# heatingHeader.net
KiCad netlist of a schematic drawn in EAGLE
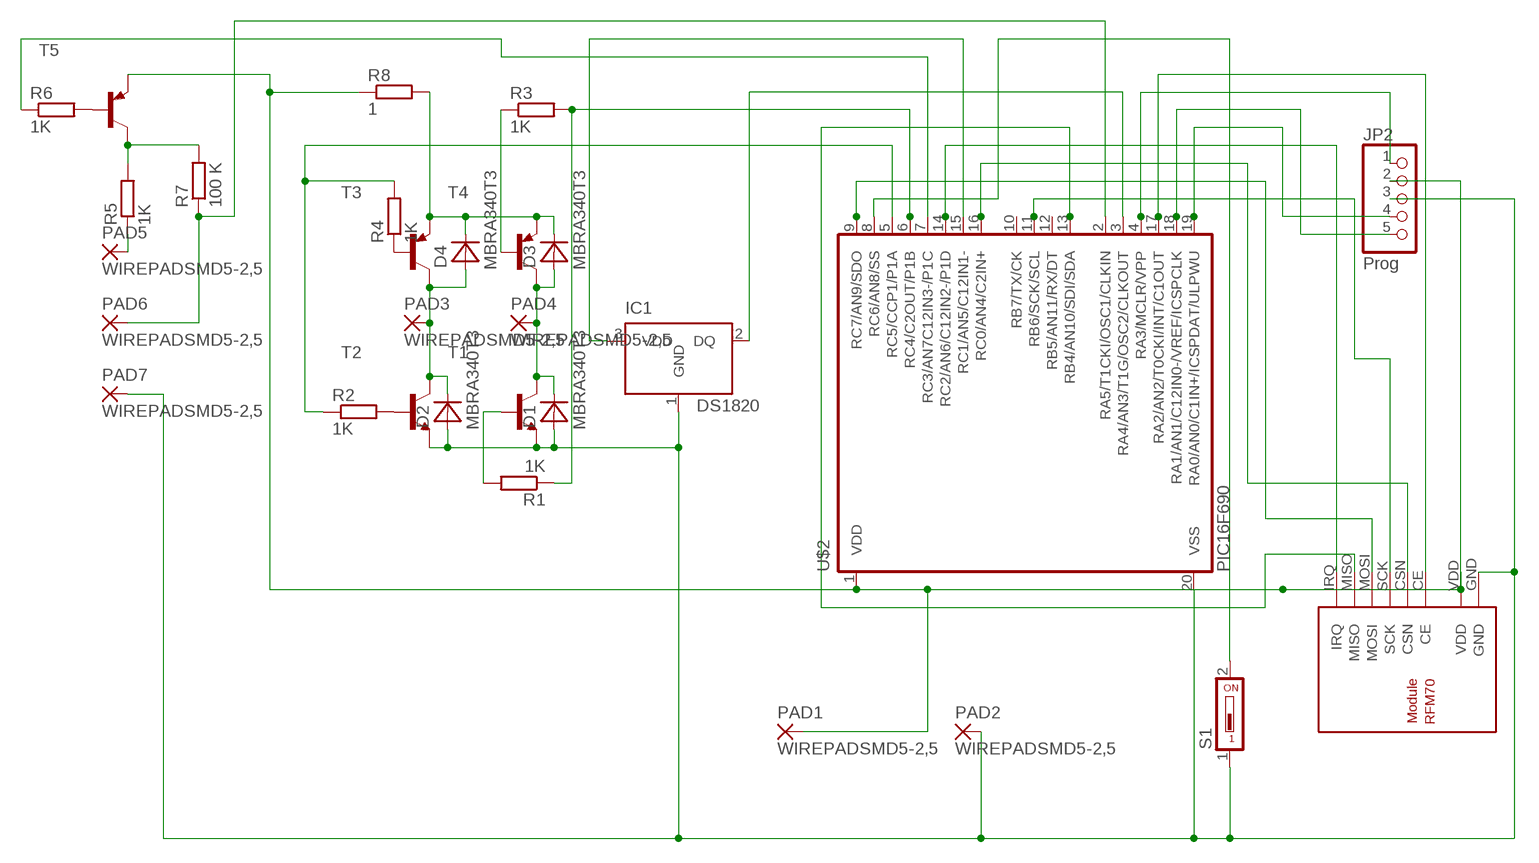
[diagram p0: schematic, sheet 1]

(export (version "E")
  (design (tool "Eeschema 10.0.6"))
  (components
    (comp (ref "D1")
      (value "MBRA340T3")
      (footprint "eagle-import:SMA")
      (libsource (lib "eagle-import") (part "MBRA340T3"))
    )
    (comp (ref "D2")
      (value "MBRA340T3")
      (footprint "eagle-import:SMA")
      (libsource (lib "eagle-import") (part "MBRA340T3"))
    )
    (comp (ref "D3")
      (value "MBRA340T3")
      (footprint "eagle-import:SMA")
      (libsource (lib "eagle-import") (part "MBRA340T3"))
    )
    (comp (ref "D4")
      (value "MBRA340T3")
      (footprint "eagle-import:SMA")
      (libsource (lib "eagle-import") (part "MBRA340T3"))
    )
    (comp (ref "IC1")
      (value "DS1820")
      (footprint "eagle-import:TO-92")
      (libsource (lib "eagle-import") (part "DS1820"))
    )
    (comp (ref "JP2")
      (value "Prog")
      (footprint "eagle-import:1X05")
      (libsource (lib "eagle-import") (part "PINHD-1X5"))
    )
    (comp (ref "PAD1")
      (value "WIREPADSMD5-2,5")
      (footprint "eagle-import:5-2,5")
      (libsource (lib "eagle-import") (part "WIREPADSMD5-2,5"))
    )
    (comp (ref "PAD2")
      (value "WIREPADSMD5-2,5")
      (footprint "eagle-import:5-2,5")
      (libsource (lib "eagle-import") (part "WIREPADSMD5-2,5"))
    )
    (comp (ref "PAD3")
      (value "WIREPADSMD5-2,5")
      (footprint "eagle-import:5-2,5")
      (libsource (lib "eagle-import") (part "WIREPADSMD5-2,5"))
    )
    (comp (ref "PAD4")
      (value "WIREPADSMD5-2,5")
      (footprint "eagle-import:5-2,5")
      (libsource (lib "eagle-import") (part "WIREPADSMD5-2,5"))
    )
    (comp (ref "PAD5")
      (value "WIREPADSMD5-2,5")
      (footprint "eagle-import:5-2,5")
      (libsource (lib "eagle-import") (part "WIREPADSMD5-2,5"))
    )
    (comp (ref "PAD6")
      (value "WIREPADSMD5-2,5")
      (footprint "eagle-import:5-2,5")
      (libsource (lib "eagle-import") (part "WIREPADSMD5-2,5"))
    )
    (comp (ref "PAD7")
      (value "WIREPADSMD5-2,5")
      (footprint "eagle-import:5-2,5")
      (libsource (lib "eagle-import") (part "WIREPADSMD5-2,5"))
    )
    (comp (ref "R1")
      (value "1K")
      (footprint "eagle-import:R1206")
      (libsource (lib "eagle-import") (part "R-EU_R1206"))
    )
    (comp (ref "R2")
      (value "1K")
      (footprint "eagle-import:R1206")
      (libsource (lib "eagle-import") (part "R-EU_R1206"))
    )
    (comp (ref "R3")
      (value "1K")
      (footprint "eagle-import:R1206")
      (libsource (lib "eagle-import") (part "R-EU_R1206"))
    )
    (comp (ref "R4")
      (value "1K")
      (footprint "eagle-import:R1206")
      (libsource (lib "eagle-import") (part "R-EU_R1206"))
    )
    (comp (ref "R5")
      (value "1K")
      (footprint "eagle-import:R1206")
      (libsource (lib "eagle-import") (part "R-EU_R1206"))
    )
    (comp (ref "R6")
      (value "1K")
      (footprint "eagle-import:R1206")
      (libsource (lib "eagle-import") (part "R-EU_R1206"))
    )
    (comp (ref "R7")
      (value "100 K")
      (footprint "eagle-import:R1206")
      (libsource (lib "eagle-import") (part "R-EU_R1206"))
    )
    (comp (ref "R8")
      (value "1")
      (footprint "eagle-import:R0805W")
      (libsource (lib "eagle-import") (part "R-EU_R0805W"))
    )
    (comp (ref "S1")
      (value "SD4-01")
      (footprint "eagle-import:SD4-01")
      (libsource (lib "eagle-import") (part "SD4-01"))
    )
    (comp (ref "T1")
      (value "BC817-40-NPN-SOT23-BEC")
      (footprint "eagle-import:SOT23-BEC")
      (libsource (lib "eagle-import") (part "-NPN-SOT23-BECBC817-40"))
    )
    (comp (ref "T2")
      (value "BC817-40-NPN-SOT23-BEC")
      (footprint "eagle-import:SOT23-BEC")
      (libsource (lib "eagle-import") (part "-NPN-SOT23-BECBC817-40"))
    )
    (comp (ref "T3")
      (value "BC807-16-PNP-SOT23-BEC")
      (footprint "eagle-import:SOT23-BEC")
      (libsource (lib "eagle-import") (part "-PNP-SOT23-BECBC807-16"))
    )
    (comp (ref "T4")
      (value "BC807-16-PNP-SOT23-BEC")
      (footprint "eagle-import:SOT23-BEC")
      (libsource (lib "eagle-import") (part "-PNP-SOT23-BECBC807-16"))
    )
    (comp (ref "T5")
      (value "BC807-16-PNP-SOT23-BEC")
      (footprint "eagle-import:SOT23-BEC")
      (libsource (lib "eagle-import") (part "-PNP-SOT23-BECBC807-16"))
    )
    (comp (ref "U$1")
      (value "RFM70")
      (footprint "eagle-import:RFM70")
      (libsource (lib "eagle-import") (part "RFM70"))
    )
    (comp (ref "U$2")
      (value "PIC16F690")
      (footprint "eagle-import:SSOP20")
      (libsource (lib "eagle-import") (part "PIC16F690"))
    )
  )
  (nets
    (net (code "1") (name "Net-(D3-PadC)") (class "Default")
      (node (ref "D3") (pin "C") (pinfunction "C_C") (pintype "passive"))
      (node (ref "D4") (pin "C") (pinfunction "C_C") (pintype "passive"))
      (node (ref "R8") (pin "2") (pinfunction "2_2") (pintype "passive"))
      (node (ref "T3") (pin "E") (pinfunction "E_E") (pintype "passive"))
      (node (ref "T4") (pin "E") (pinfunction "E_E") (pintype "passive"))
    )
    (net (code "2") (name "Net-(IC1-DQ)") (class "Default")
      (node (ref "IC1") (pin "2") (pinfunction "DQ_2") (pintype "output"))
      (node (ref "U$2") (pin "3") (pinfunction "RA4/AN3/T1G/OSC2/CLKOUT_3") (pintype "bidirectional"))
    )
    (net (code "3") (name "Net-(IC1-GND)") (class "Default")
      (node (ref "D1") (pin "A") (pinfunction "A_A") (pintype "passive"))
      (node (ref "D2") (pin "A") (pinfunction "A_A") (pintype "passive"))
      (node (ref "IC1") (pin "1") (pinfunction "GND_1") (pintype "power_in"))
      (node (ref "JP2") (pin "3") (pinfunction "3_3") (pintype "passive"))
      (node (ref "PAD2") (pin "1") (pinfunction "P_1") (pintype "passive"))
      (node (ref "PAD7") (pin "1") (pinfunction "P_1") (pintype "passive"))
      (node (ref "S1") (pin "1") (pinfunction "1_1") (pintype "passive"))
      (node (ref "T1") (pin "E") (pinfunction "E_E") (pintype "passive"))
      (node (ref "T2") (pin "E") (pinfunction "E_E") (pintype "passive"))
      (node (ref "U$1") (pin "GND") (pinfunction "GND_GND") (pintype "power_in"))
      (node (ref "U$2") (pin "20") (pinfunction "VSS_20") (pintype "power_in"))
    )
    (net (code "4") (name "Net-(IC1-VDD)") (class "Default")
      (node (ref "IC1") (pin "3") (pinfunction "VDD_3") (pintype "input"))
      (node (ref "U$2") (pin "15") (pinfunction "RC1/AN5/C12IN1-_15") (pintype "bidirectional"))
    )
    (net (code "5") (name "Net-(PAD1-P)") (class "Default")
      (node (ref "JP2") (pin "2") (pinfunction "2_2") (pintype "passive"))
      (node (ref "PAD1") (pin "1") (pinfunction "P_1") (pintype "passive"))
      (node (ref "R8") (pin "1") (pinfunction "1_1") (pintype "passive"))
      (node (ref "T5") (pin "E") (pinfunction "E_E") (pintype "passive"))
      (node (ref "U$1") (pin "VDD") (pinfunction "VDD_VDD") (pintype "power_in"))
      (node (ref "U$2") (pin "1") (pinfunction "VDD_1") (pintype "power_in"))
    )
    (net (code "6") (name "Net-(PAD3-P)") (class "Default")
      (node (ref "D2") (pin "C") (pinfunction "C_C") (pintype "passive"))
      (node (ref "D4") (pin "A") (pinfunction "A_A") (pintype "passive"))
      (node (ref "PAD3") (pin "1") (pinfunction "P_1") (pintype "passive"))
      (node (ref "T2") (pin "C") (pinfunction "C_C") (pintype "passive"))
      (node (ref "T3") (pin "C") (pinfunction "C_C") (pintype "passive"))
    )
    (net (code "7") (name "Net-(PAD4-P)") (class "Default")
      (node (ref "D1") (pin "C") (pinfunction "C_C") (pintype "passive"))
      (node (ref "D3") (pin "A") (pinfunction "A_A") (pintype "passive"))
      (node (ref "PAD4") (pin "1") (pinfunction "P_1") (pintype "passive"))
      (node (ref "T1") (pin "C") (pinfunction "C_C") (pintype "passive"))
      (node (ref "T4") (pin "C") (pinfunction "C_C") (pintype "passive"))
    )
    (net (code "8") (name "Net-(PAD5-P)") (class "Default")
      (node (ref "PAD5") (pin "1") (pinfunction "P_1") (pintype "passive"))
      (node (ref "R5") (pin "1") (pinfunction "1_1") (pintype "passive"))
    )
    (net (code "9") (name "Net-(PAD6-P)") (class "Default")
      (node (ref "PAD6") (pin "1") (pinfunction "P_1") (pintype "passive"))
      (node (ref "R7") (pin "1") (pinfunction "1_1") (pintype "passive"))
      (node (ref "U$2") (pin "2") (pinfunction "RA5/T1CKI/OSC1/CLKIN_2") (pintype "bidirectional"))
    )
    (net (code "10") (name "Net-(R1-Pad2)") (class "Default")
      (node (ref "R1") (pin "2") (pinfunction "2_2") (pintype "passive"))
      (node (ref "T1") (pin "B") (pinfunction "B_B") (pintype "passive"))
    )
    (net (code "11") (name "Net-(R2-Pad2)") (class "Default")
      (node (ref "R2") (pin "2") (pinfunction "2_2") (pintype "passive"))
      (node (ref "T2") (pin "B") (pinfunction "B_B") (pintype "passive"))
    )
    (net (code "12") (name "Net-(R3-Pad1)") (class "Default")
      (node (ref "R3") (pin "1") (pinfunction "1_1") (pintype "passive"))
      (node (ref "T4") (pin "B") (pinfunction "B_B") (pintype "passive"))
    )
    (net (code "13") (name "Net-(R4-Pad1)") (class "Default")
      (node (ref "R4") (pin "1") (pinfunction "1_1") (pintype "passive"))
      (node (ref "T3") (pin "B") (pinfunction "B_B") (pintype "passive"))
    )
    (net (code "14") (name "Net-(R5-Pad2)") (class "Default")
      (node (ref "R5") (pin "2") (pinfunction "2_2") (pintype "passive"))
      (node (ref "R7") (pin "2") (pinfunction "2_2") (pintype "passive"))
      (node (ref "T5") (pin "C") (pinfunction "C_C") (pintype "passive"))
    )
    (net (code "15") (name "Net-(R6-Pad2)") (class "Default")
      (node (ref "R6") (pin "2") (pinfunction "2_2") (pintype "passive"))
      (node (ref "T5") (pin "B") (pinfunction "B_B") (pintype "passive"))
    )
    (net (code "16") (name "Net-(U$2-RA0{slash}AN0{slash}C1IN+{slash}ICSPDAT{slash}ULPWU)") (class "Default")
      (node (ref "JP2") (pin "4") (pinfunction "4_4") (pintype "passive"))
      (node (ref "U$2") (pin "19") (pinfunction "RA0/AN0/C1IN+/ICSPDAT/ULPWU_19") (pintype "bidirectional"))
    )
    (net (code "17") (name "Net-(U$2-RA1{slash}AN1{slash}C12IN0-{slash}VREF{slash}ICSPCLK)") (class "Default")
      (node (ref "JP2") (pin "5") (pinfunction "5_5") (pintype "passive"))
      (node (ref "U$2") (pin "18") (pinfunction "RA1/AN1/C12IN0-/VREF/ICSPCLK_18") (pintype "bidirectional"))
    )
    (net (code "18") (name "Net-(U$2-RA2{slash}AN2{slash}T0CKI{slash}INT{slash}C1OUT)") (class "Default")
      (node (ref "U$1") (pin "CE") (pinfunction "CE_CE") (pintype "bidirectional"))
      (node (ref "U$2") (pin "17") (pinfunction "RA2/AN2/T0CKI/INT/C1OUT_17") (pintype "bidirectional"))
    )
    (net (code "19") (name "Net-(U$2-RA3{slash}MCLR{slash}VPP)") (class "Default")
      (node (ref "JP2") (pin "1") (pinfunction "1_1") (pintype "passive"))
      (node (ref "U$2") (pin "4") (pinfunction "RA3/MCLR/VPP_4") (pintype "bidirectional"))
    )
    (net (code "20") (name "Net-(U$2-RB4{slash}AN10{slash}SDI{slash}SDA)") (class "Default")
      (node (ref "U$1") (pin "MISO") (pinfunction "MISO_MISO") (pintype "bidirectional"))
      (node (ref "U$2") (pin "13") (pinfunction "RB4/AN10/SDI/SDA_13") (pintype "bidirectional"))
    )
    (net (code "21") (name "Net-(U$2-RB6{slash}SCK{slash}SCL)") (class "Default")
      (node (ref "U$1") (pin "SCK") (pinfunction "SCK_SCK") (pintype "bidirectional"))
      (node (ref "U$2") (pin "11") (pinfunction "RB6/SCK/SCL_11") (pintype "bidirectional"))
    )
    (net (code "22") (name "Net-(U$2-RC0{slash}AN4{slash}C2IN+)") (class "Default")
      (node (ref "U$1") (pin "CSN") (pinfunction "CSN_CSN") (pintype "bidirectional"))
      (node (ref "U$2") (pin "16") (pinfunction "RC0/AN4/C2IN+_16") (pintype "bidirectional"))
    )
    (net (code "23") (name "Net-(U$2-RC2{slash}AN6{slash}C12IN2-{slash}P1D)") (class "Default")
      (node (ref "U$1") (pin "IRQ") (pinfunction "IRQ_IRQ") (pintype "bidirectional"))
      (node (ref "U$2") (pin "14") (pinfunction "RC2/AN6/C12IN2-/P1D_14") (pintype "bidirectional"))
    )
    (net (code "24") (name "Net-(U$2-RC3{slash}AN7C12IN3-{slash}P1C)") (class "Default")
      (node (ref "R6") (pin "1") (pinfunction "1_1") (pintype "passive"))
      (node (ref "U$2") (pin "7") (pinfunction "RC3/AN7C12IN3-/P1C_7") (pintype "bidirectional"))
    )
    (net (code "25") (name "Net-(U$2-RC4{slash}C2OUT{slash}P1B)") (class "Default")
      (node (ref "R1") (pin "1") (pinfunction "1_1") (pintype "passive"))
      (node (ref "R3") (pin "2") (pinfunction "2_2") (pintype "passive"))
      (node (ref "U$2") (pin "6") (pinfunction "RC4/C2OUT/P1B_6") (pintype "bidirectional"))
    )
    (net (code "26") (name "Net-(U$2-RC5{slash}CCP1{slash}P1A)") (class "Default")
      (node (ref "R2") (pin "1") (pinfunction "1_1") (pintype "passive"))
      (node (ref "R4") (pin "2") (pinfunction "2_2") (pintype "passive"))
      (node (ref "U$2") (pin "5") (pinfunction "RC5/CCP1/P1A_5") (pintype "bidirectional"))
    )
    (net (code "27") (name "Net-(U$2-RC6{slash}AN8{slash}SS)") (class "Default")
      (node (ref "S1") (pin "2") (pinfunction "2_2") (pintype "passive"))
      (node (ref "U$2") (pin "8") (pinfunction "RC6/AN8/SS_8") (pintype "bidirectional"))
    )
    (net (code "28") (name "Net-(U$2-RC7{slash}AN9{slash}SDO)") (class "Default")
      (node (ref "U$1") (pin "MOSI") (pinfunction "MOSI_MOSI") (pintype "bidirectional"))
      (node (ref "U$2") (pin "9") (pinfunction "RC7/AN9/SDO_9") (pintype "bidirectional"))
    )
    (net (code "29") (name "unconnected-(U$2-RB5{slash}AN11{slash}RX{slash}DT-Pad12)") (class "Default")
      (node (ref "U$2") (pin "12") (pinfunction "RB5/AN11/RX/DT_12") (pintype "bidirectional"))
    )
    (net (code "30") (name "unconnected-(U$2-RB7{slash}TX{slash}CK-Pad10)") (class "Default")
      (node (ref "U$2") (pin "10") (pinfunction "RB7/TX/CK_10") (pintype "bidirectional"))
    )
  )
)
